# 5_3_frontend.net
KiCad netlist of a schematic drawn in Altium Designer
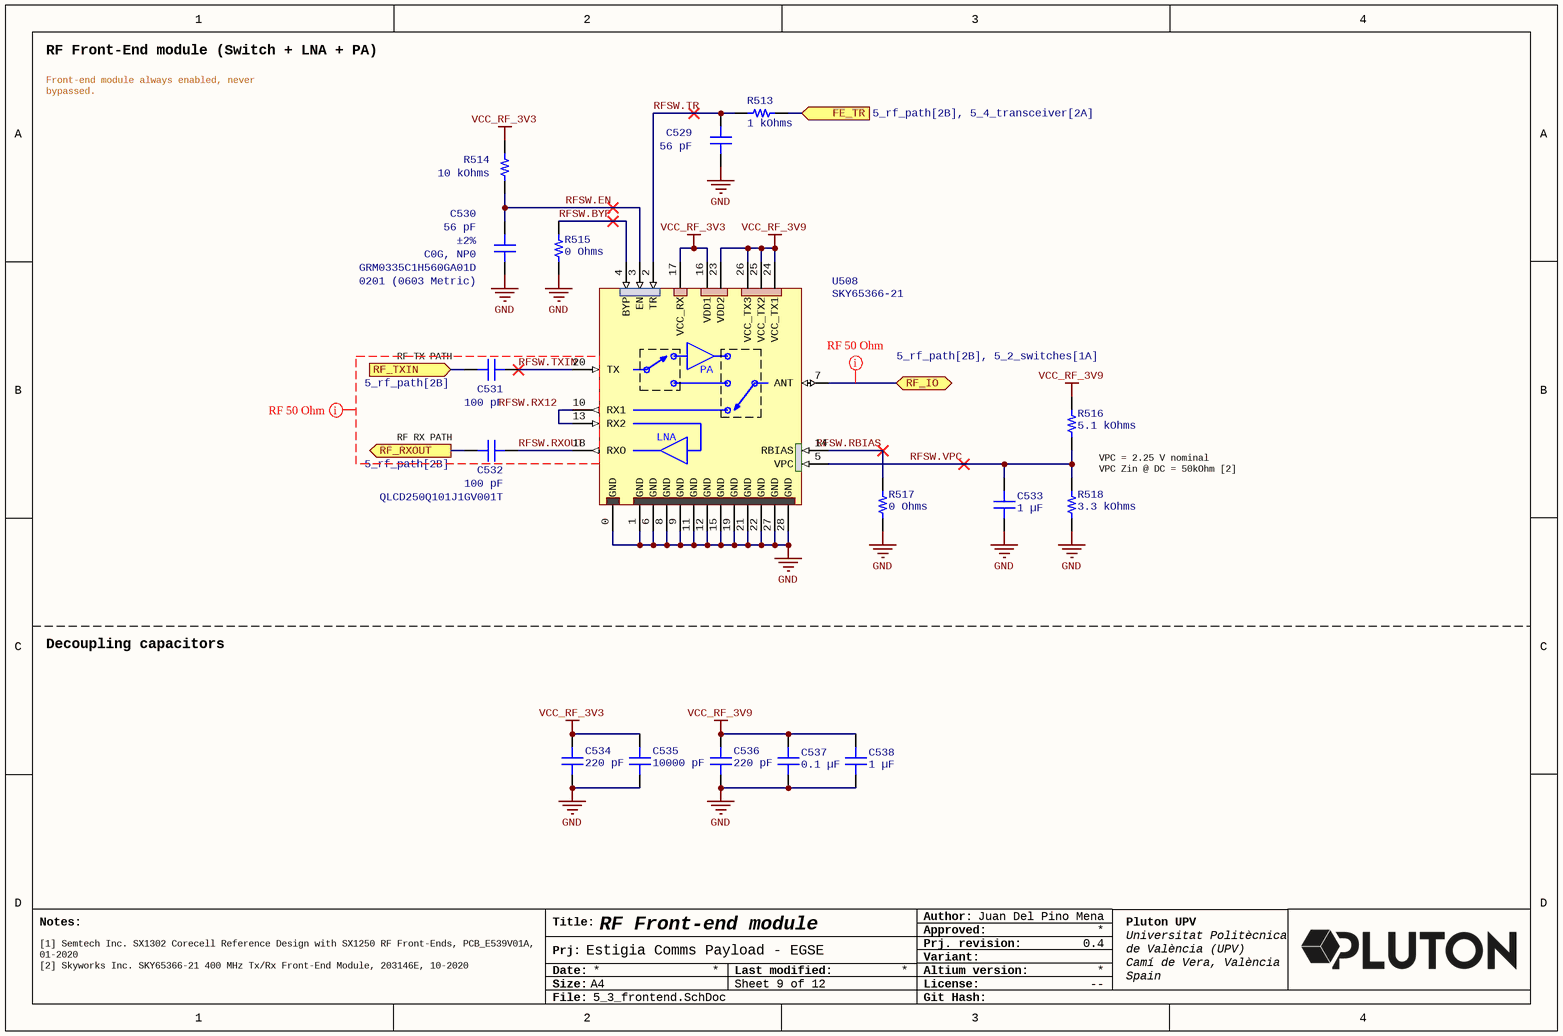
[diagram p0: 5_3_frontend.SchDoc]

(export (version "E")
  (design (tool "Eeschema 10.0.6"))
  (components
    (comp (ref "C529")
      (value "56 pF")
      (footprint "CAP 0201_0603")
      (description "CAP CER 56PF 50V C0G/NP0 0201")
      (fields
        (field (name "PART NUMBER") "GRM0335C1H560GA01D")
        (field (name "MANUFACTURER") "Murata Electronics")
      )
      (libsource (lib "Celestial Altium Library - altium_library") (part "Capacitor"))
    )
    (comp (ref "C530")
      (value "56 pF")
      (footprint "CAP 0201_0603")
      (description "CAP CER 56PF 50V C0G/NP0 0201")
      (fields
        (field (name "PART NUMBER") "GRM0335C1H560GA01D")
        (field (name "MANUFACTURER") "Murata Electronics")
        (field (name "PACKAGE / CASE") "0201 (0603 Metric)")
        (field (name "TEMPERATURE COEFFICIENT") "C0G, NP0")
        (field (name "TOLERANCE") "±2%")
      )
      (libsource (lib "Celestial Altium Library - altium_library") (part "Capacitor"))
    )
    (comp (ref "C531")
      (value "100 pF")
      (footprint "CAP 0201_0603 RF")
      (description "CAP CER 100PF 25V C0G/NP0 0201")
      (fields
        (field (name "PART NUMBER") "QLCD250Q101J1GV001T")
        (field (name "CAPACITANCE") "100 pF")
        (field (name "MANUFACTURER") "Johanson Technology Inc.")
        (field (name "TOLERANCE") "±5%")
      )
      (libsource (lib "Celestial Altium Library - altium_library") (part "Capacitor"))
    )
    (comp (ref "C532")
      (value "100 pF")
      (footprint "CAP 0201_0603 RF")
      (description "CAP CER 100PF 25V C0G/NP0 0201")
      (fields
        (field (name "PART NUMBER") "QLCD250Q101J1GV001T")
        (field (name "CAPACITANCE") "100 pF")
        (field (name "MANUFACTURER") "Johanson Technology Inc.")
      )
      (libsource (lib "Celestial Altium Library - altium_library") (part "Capacitor"))
    )
    (comp (ref "C533")
      (value "1 µF")
      (footprint "CAP 0402_1005")
      (description "CAP CER 1UF 16V X5R 0402")
      (fields
        (field (name "PART NUMBER") "CL05A105KO5NNNC")
        (field (name "MANUFACTURER") "Samsung Electro-Mechanics")
      )
      (libsource (lib "Celestial Altium Library - altium_library") (part "Capacitor"))
    )
    (comp (ref "C534")
      (value "220 pF")
      (footprint "CAP 0201_0603")
      (description "CAP CER 220PF 50V C0G/NP0 0201")
      (fields
        (field (name "PART NUMBER") "GRM0335C1H221JA01D")
        (field (name "MANUFACTURER") "Murata Electronics")
      )
      (libsource (lib "Celestial Altium Library - altium_library") (part "Capacitor"))
    )
    (comp (ref "C535")
      (value "10000 pF")
      (footprint "CAP 0402_1005")
      (description "CAP CER 10000PF 25V C0G/NP0 0402")
      (fields
        (field (name "PART NUMBER") "GRM1555C1E103JE01J")
        (field (name "MANUFACTURER") "Murata Electronics")
      )
      (libsource (lib "Celestial Altium Library - altium_library") (part "Capacitor"))
    )
    (comp (ref "C536")
      (value "220 pF")
      (footprint "CAP 0201_0603")
      (description "CAP CER 220PF 50V C0G/NP0 0201")
      (fields
        (field (name "PART NUMBER") "GRM0335C1H221JA01D")
        (field (name "MANUFACTURER") "Murata Electronics")
      )
      (libsource (lib "Celestial Altium Library - altium_library") (part "Capacitor"))
    )
    (comp (ref "C537")
      (value "0.1 µF")
      (footprint "CAP 0402_1005")
      (description "CAP CER 0402 0.1UF 16V X7R 10%")
      (fields (field (name "PART NUMBER") "C0402C104K4RECAUTO") (field (name "MANUFACTURER") "KEMET"))
      (libsource (lib "Celestial Altium Library - altium_library") (part "Capacitor"))
    )
    (comp (ref "C538")
      (value "1 µF")
      (footprint "CAP 0402_1005")
      (description "CAP CER 1UF 10V X7S 0402")
      (fields
        (field (name "PART NUMBER") "GRT155C71A105KE13D")
        (field (name "MANUFACTURER") "Murata Electronics")
      )
      (libsource (lib "Celestial Altium Library - altium_library") (part "Capacitor"))
    )
    (comp (ref "R513")
      (value "1 kOhms")
      (footprint "RES 0201_0603")
      (description "RES SMD 1K OHM 1% 1/20W 0201")
      (fields (field (name "PART NUMBER") "AC0201FR-071KL") (field (name "MANUFACTURER") "Yageo"))
      (libsource (lib "Celestial Altium Library - altium_library") (part "Resistor"))
    )
    (comp (ref "R514")
      (value "10 kOhms")
      (footprint "RES 0201_0603")
      (description "RES SMD 10K OHM 1% 1/20W 0201")
      (fields (field (name "PART NUMBER") "AF0201FR-0710KL") (field (name "MANUFACTURER") "Yageo"))
      (libsource (lib "Celestial Altium Library - altium_library") (part "Resistor"))
    )
    (comp (ref "R515")
      (value "0 Ohms")
      (footprint "RES 0201_0603")
      (description "RES SMD 0 OHM JUMPER 1/20W 0201")
      (fields (field (name "PART NUMBER") "AC0201JR-070RL") (field (name "MANUFACTURER") "Yageo"))
      (libsource (lib "Celestial Altium Library - altium_library") (part "Resistor"))
    )
    (comp (ref "R516")
      (value "5.1 kOhms")
      (footprint "RES 0201_0603")
      (description "RES SMD 5.1K OHM 1% 1/20W 0201")
      (fields
        (field (name "PART NUMBER") "ERJ-1GNF5101C")
        (field (name "MANUFACTURER") "Panasonic Electronic Components")
      )
      (libsource (lib "Celestial Altium Library - altium_library") (part "Resistor"))
    )
    (comp (ref "R517")
      (value "0 Ohms")
      (footprint "RES 0201_0603")
      (description "RES SMD 0 OHM JUMPER 1/20W 0201")
      (fields (field (name "PART NUMBER") "AC0201JR-070RL") (field (name "MANUFACTURER") "Yageo"))
      (libsource (lib "Celestial Altium Library - altium_library") (part "Resistor"))
    )
    (comp (ref "R518")
      (value "3.3 kOhms")
      (footprint "RES 0201_0603")
      (description "RES SMD 3.3K OHM 1% 1/20W 0201")
      (fields
        (field (name "PART NUMBER") "ERJ-1GJF3301C")
        (field (name "MANUFACTURER") "Panasonic Electronic Components")
      )
      (libsource (lib "Celestial Altium Library - altium_library") (part "Resistor"))
    )
    (comp (ref "U508")
      (value "SKY65366-21")
      (footprint "MCM-28-SKY65366-21")
      (description "400 MHz Transmit/Receive Front-End Module")
      (libsource (lib "rf") (part "SKY65366-21"))
    )
  )
  (nets
    (net (code "1") (name "/FE_TR") (class "Default")
      (node (ref "R513") (pin "2") (pinfunction "2_2") (pintype "passive"))
    )
    (net (code "4") (name "/RFSW.BYP") (class "Default")
      (node (ref "R515") (pin "2") (pinfunction "2_2") (pintype "passive"))
      (node (ref "U508") (pin "4") (pinfunction "BYP_4") (pintype "input"))
    )
    (net (code "5") (name "/RFSW.EN") (class "Default")
      (node (ref "C530") (pin "2") (pinfunction "2_2") (pintype "passive"))
      (node (ref "R514") (pin "1") (pinfunction "1_1") (pintype "passive"))
      (node (ref "U508") (pin "3") (pinfunction "EN_3") (pintype "input"))
    )
    (net (code "6") (name "/RFSW.RBIAS") (class "Default")
      (node (ref "R517") (pin "2") (pinfunction "2_2") (pintype "passive"))
      (node (ref "U508") (pin "14") (pinfunction "RBIAS_14") (pintype "input"))
    )
    (net (code "7") (name "/RFSW.RX12") (class "Default")
      (node (ref "U508") (pin "10") (pinfunction "RX1_10") (pintype "output"))
      (node (ref "U508") (pin "13") (pinfunction "RX2_13") (pintype "input"))
    )
    (net (code "8") (name "/RFSW.RXOUT") (class "Default")
      (node (ref "C532") (pin "2") (pinfunction "2_2") (pintype "passive"))
      (node (ref "U508") (pin "18") (pinfunction "RXO_18") (pintype "output"))
    )
    (net (code "10") (name "/RFSW.TR") (class "Default")
      (node (ref "C529") (pin "2") (pinfunction "2_2") (pintype "passive"))
      (node (ref "R513") (pin "1") (pinfunction "1_1") (pintype "passive"))
      (node (ref "U508") (pin "2") (pinfunction "TR_2") (pintype "input"))
    )
    (net (code "11") (name "/RFSW.TXIN") (class "Default")
      (node (ref "C531") (pin "2") (pinfunction "2_2") (pintype "passive"))
      (node (ref "U508") (pin "20") (pinfunction "TX_20") (pintype "input"))
    )
    (net (code "12") (name "/RFSW.VPC") (class "Default")
      (node (ref "C533") (pin "2") (pinfunction "2_2") (pintype "passive"))
      (node (ref "R516") (pin "1") (pinfunction "1_1") (pintype "passive"))
      (node (ref "R518") (pin "2") (pinfunction "2_2") (pintype "passive"))
      (node (ref "U508") (pin "5") (pinfunction "VPC_5") (pintype "input"))
    )
    (net (code "13") (name "/RF_IO") (class "Default")
      (node (ref "U508") (pin "7") (pinfunction "ANT_7") (pintype "bidirectional"))
    )
    (net (code "14") (name "/RF_RXOUT") (class "Default")
      (node (ref "C532") (pin "1") (pinfunction "1_1") (pintype "passive"))
    )
    (net (code "15") (name "/RF_TXIN") (class "Default")
      (node (ref "C531") (pin "1") (pinfunction "1_1") (pintype "passive"))
    )
    (net (code "16") (name "GND") (class "Default")
      (node (ref "C529") (pin "1") (pinfunction "1_1") (pintype "passive"))
      (node (ref "C530") (pin "1") (pinfunction "1_1") (pintype "passive"))
      (node (ref "C533") (pin "1") (pinfunction "1_1") (pintype "passive"))
      (node (ref "C534") (pin "1") (pinfunction "1_1") (pintype "passive"))
      (node (ref "C535") (pin "1") (pinfunction "1_1") (pintype "passive"))
      (node (ref "C536") (pin "1") (pinfunction "1_1") (pintype "passive"))
      (node (ref "C537") (pin "1") (pinfunction "1_1") (pintype "passive"))
      (node (ref "C538") (pin "1") (pinfunction "1_1") (pintype "passive"))
      (node (ref "R515") (pin "1") (pinfunction "1_1") (pintype "passive"))
      (node (ref "R517") (pin "1") (pinfunction "1_1") (pintype "passive"))
      (node (ref "R518") (pin "1") (pinfunction "1_1") (pintype "passive"))
      (node (ref "U508") (pin "0") (pinfunction "GND_0") (pintype "power_in"))
      (node (ref "U508") (pin "1") (pinfunction "GND_1") (pintype "power_in"))
      (node (ref "U508") (pin "11") (pinfunction "GND_11") (pintype "power_in"))
      (node (ref "U508") (pin "12") (pinfunction "GND_12") (pintype "power_in"))
      (node (ref "U508") (pin "15") (pinfunction "GND_15") (pintype "power_in"))
      (node (ref "U508") (pin "19") (pinfunction "GND_19") (pintype "power_in"))
      (node (ref "U508") (pin "21") (pinfunction "GND_21") (pintype "power_in"))
      (node (ref "U508") (pin "22") (pinfunction "GND_22") (pintype "power_in"))
      (node (ref "U508") (pin "27") (pinfunction "GND_27") (pintype "power_in"))
      (node (ref "U508") (pin "28") (pinfunction "GND_28") (pintype "power_in"))
      (node (ref "U508") (pin "6") (pinfunction "GND_6") (pintype "power_in"))
      (node (ref "U508") (pin "8") (pinfunction "GND_8") (pintype "power_in"))
      (node (ref "U508") (pin "9") (pinfunction "GND_9") (pintype "power_in"))
    )
    (net (code "17") (name "VCC_RF_3V3") (class "Default")
      (node (ref "C534") (pin "2") (pinfunction "2_2") (pintype "passive"))
      (node (ref "C535") (pin "2") (pinfunction "2_2") (pintype "passive"))
      (node (ref "R514") (pin "2") (pinfunction "2_2") (pintype "passive"))
      (node (ref "U508") (pin "16") (pinfunction "VDD1_16") (pintype "power_in"))
      (node (ref "U508") (pin "17") (pinfunction "VCC_RX_17") (pintype "power_in"))
    )
    (net (code "18") (name "VCC_RF_3V9") (class "Default")
      (node (ref "C536") (pin "2") (pinfunction "2_2") (pintype "passive"))
      (node (ref "C537") (pin "2") (pinfunction "2_2") (pintype "passive"))
      (node (ref "C538") (pin "2") (pinfunction "2_2") (pintype "passive"))
      (node (ref "R516") (pin "2") (pinfunction "2_2") (pintype "passive"))
      (node (ref "U508") (pin "23") (pinfunction "VDD2_23") (pintype "power_in"))
      (node (ref "U508") (pin "24") (pinfunction "VCC_TX1_24") (pintype "power_in"))
      (node (ref "U508") (pin "25") (pinfunction "VCC_TX2_25") (pintype "power_in"))
      (node (ref "U508") (pin "26") (pinfunction "VCC_TX3_26") (pintype "power_in"))
    )
  )
)
